# CREE_usb_LED.net
KiCad netlist of a schematic drawn in EAGLE
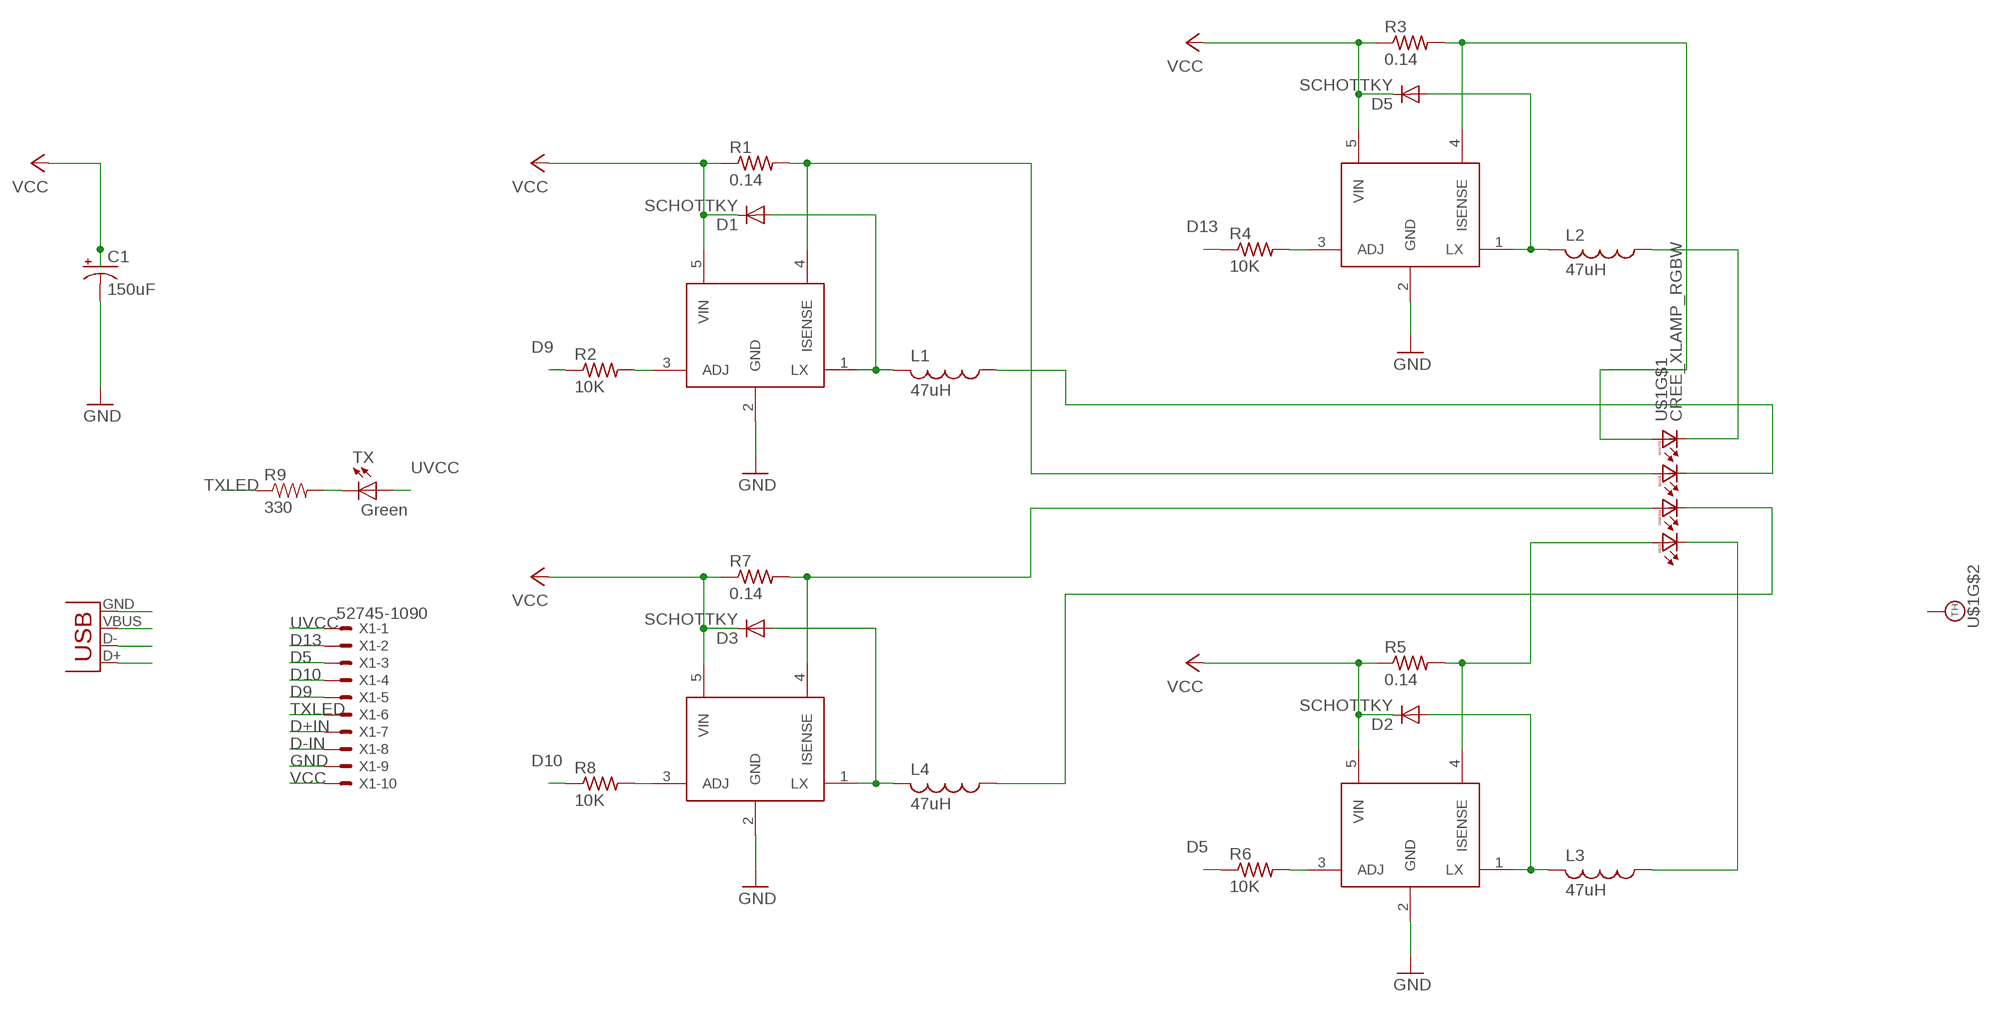
[diagram p0: schematic, sheet 1]

(export (version "E")
  (design (tool "Eeschema 10.0.6"))
  (components
    (comp (ref "C1")
      (value "150uF")
      (footprint "eagle-import:175TMP-0810")
      (libsource (lib "eagle-import") (part "CPOL-US175TMP-0810"))
    )
    (comp (ref "D1")
      (value "SCHOTTKY")
      (footprint "eagle-import:DO214AC")
      (libsource (lib "eagle-import") (part "DIODE-DO214AC"))
    )
    (comp (ref "D2")
      (value "SCHOTTKY")
      (footprint "eagle-import:DO214AC")
      (libsource (lib "eagle-import") (part "DIODE-DO214AC"))
    )
    (comp (ref "D3")
      (value "SCHOTTKY")
      (footprint "eagle-import:DO214AC")
      (libsource (lib "eagle-import") (part "DIODE-DO214AC"))
    )
    (comp (ref "D5")
      (value "SCHOTTKY")
      (footprint "eagle-import:DO214AC")
      (libsource (lib "eagle-import") (part "DIODE-DO214AC"))
    )
    (comp (ref "L1")
      (value "47uH")
      (footprint "eagle-import:TDK6045")
      (libsource (lib "eagle-import") (part "L-US"))
    )
    (comp (ref "L2")
      (value "47uH")
      (footprint "eagle-import:TDK6045")
      (libsource (lib "eagle-import") (part "L-US"))
    )
    (comp (ref "L3")
      (value "47uH")
      (footprint "eagle-import:TDK6045")
      (libsource (lib "eagle-import") (part "L-US"))
    )
    (comp (ref "L4")
      (value "47uH")
      (footprint "eagle-import:TDK6045")
      (libsource (lib "eagle-import") (part "L-US"))
    )
    (comp (ref "R1")
      (value "0.14")
      (footprint "eagle-import:R0805")
      (libsource (lib "eagle-import") (part "R-US_R0805"))
    )
    (comp (ref "R2")
      (value "10K")
      (footprint "eagle-import:R0603")
      (libsource (lib "eagle-import") (part "R-US_R0603"))
    )
    (comp (ref "R3")
      (value "0.14")
      (footprint "eagle-import:R0805")
      (libsource (lib "eagle-import") (part "R-US_R0805"))
    )
    (comp (ref "R4")
      (value "10K")
      (footprint "eagle-import:R0603")
      (libsource (lib "eagle-import") (part "R-US_R0603"))
    )
    (comp (ref "R5")
      (value "0.14")
      (footprint "eagle-import:R0805")
      (libsource (lib "eagle-import") (part "R-US_R0805"))
    )
    (comp (ref "R6")
      (value "10K")
      (footprint "eagle-import:R0603")
      (libsource (lib "eagle-import") (part "R-US_R0603"))
    )
    (comp (ref "R7")
      (value "0.14")
      (footprint "eagle-import:R0805")
      (libsource (lib "eagle-import") (part "R-US_R0805"))
    )
    (comp (ref "R8")
      (value "10K")
      (footprint "eagle-import:R0603")
      (libsource (lib "eagle-import") (part "R-US_R0603"))
    )
    (comp (ref "R9")
      (value "330")
      (footprint "eagle-import:0402-RES")
      (libsource (lib "eagle-import") (part "RESISTOR0402-RES"))
    )
    (comp (ref "TX")
      (value "Green")
      (footprint "eagle-import:LED-0603")
      (libsource (lib "eagle-import") (part "LED0603"))
    )
    (comp (ref "U$1")
      (value "CREE_XLAMP_RGBW")
      (footprint "eagle-import:CREE_XLAMP_XML")
      (libsource (lib "eagle-import") (part "CREE_XLAMP_RGBW"))
    )
    (comp (ref "U$2")
      (value "ZLED7000-LEDDRIVER")
      (footprint "eagle-import:SOT89-5")
      (libsource (lib "eagle-import") (part "ZLED7000-LEDDRIVER"))
    )
    (comp (ref "U$3")
      (value "ZLED7000-LEDDRIVER")
      (footprint "eagle-import:SOT89-5")
      (libsource (lib "eagle-import") (part "ZLED7000-LEDDRIVER"))
    )
    (comp (ref "U$4")
      (value "ZLED7000-LEDDRIVER")
      (footprint "eagle-import:SOT89-5")
      (libsource (lib "eagle-import") (part "ZLED7000-LEDDRIVER"))
    )
    (comp (ref "U$6")
      (value "ZLED7000-LEDDRIVER")
      (footprint "eagle-import:SOT89-5")
      (libsource (lib "eagle-import") (part "ZLED7000-LEDDRIVER"))
    )
    (comp (ref "X1")
      (value "52745-1090")
      (footprint "eagle-import:52745-1090")
      (libsource (lib "eagle-import") (part "52745-1090"))
    )
    (comp (ref "X2")
      (value "USB-MICROB")
      (footprint "eagle-import:USB-MICROB")
      (libsource (lib "eagle-import") (part "USB-MICROB"))
    )
  )
  (nets
    (net (code "1") (name "/D+IN") (class "Default")
      (node (ref "X1") (pin "7") (pinfunction "S_7") (pintype "passive"))
      (node (ref "X2") (pin "D+") (pinfunction "D+_D+") (pintype "bidirectional"))
    )
    (net (code "2") (name "/D-IN") (class "Default")
      (node (ref "X1") (pin "8") (pinfunction "S_8") (pintype "passive"))
      (node (ref "X2") (pin "D-") (pinfunction "D-_D-") (pintype "bidirectional"))
    )
    (net (code "3") (name "/D5") (class "Default")
      (node (ref "R6") (pin "1") (pinfunction "1_1") (pintype "passive"))
      (node (ref "X1") (pin "3") (pinfunction "S_3") (pintype "passive"))
    )
    (net (code "4") (name "/D9") (class "Default")
      (node (ref "R2") (pin "1") (pinfunction "1_1") (pintype "passive"))
      (node (ref "X1") (pin "5") (pinfunction "S_5") (pintype "passive"))
    )
    (net (code "5") (name "/D10") (class "Default")
      (node (ref "R8") (pin "1") (pinfunction "1_1") (pintype "passive"))
      (node (ref "X1") (pin "4") (pinfunction "S_4") (pintype "passive"))
    )
    (net (code "6") (name "/D13") (class "Default")
      (node (ref "R4") (pin "1") (pinfunction "1_1") (pintype "passive"))
      (node (ref "X1") (pin "2") (pinfunction "S_2") (pintype "passive"))
    )
    (net (code "7") (name "/TXLED") (class "Default")
      (node (ref "R9") (pin "1") (pinfunction "1_1") (pintype "passive"))
      (node (ref "X1") (pin "6") (pinfunction "S_6") (pintype "passive"))
    )
    (net (code "8") (name "/UVCC") (class "Default")
      (node (ref "TX") (pin "A") (pinfunction "A_A") (pintype "passive"))
      (node (ref "X1") (pin "1") (pinfunction "S_1") (pintype "passive"))
      (node (ref "X2") (pin "VBUS") (pinfunction "VBUS_VBUS") (pintype "bidirectional"))
    )
    (net (code "9") (name "GND") (class "Default")
      (node (ref "C1") (pin "-") (pinfunction "-_-") (pintype "passive"))
      (node (ref "U$2") (pin "2") (pinfunction "GND_2") (pintype "bidirectional"))
      (node (ref "U$3") (pin "2") (pinfunction "GND_2") (pintype "bidirectional"))
      (node (ref "U$4") (pin "2") (pinfunction "GND_2") (pintype "bidirectional"))
      (node (ref "U$6") (pin "2") (pinfunction "GND_2") (pintype "bidirectional"))
      (node (ref "X1") (pin "9") (pinfunction "S_9") (pintype "passive"))
      (node (ref "X2") (pin "GND") (pinfunction "GND_GND") (pintype "bidirectional"))
    )
    (net (code "10") (name "Net-(R9-Pad2)") (class "Default")
      (node (ref "R9") (pin "2") (pinfunction "2_2") (pintype "passive"))
      (node (ref "TX") (pin "C") (pinfunction "C_C") (pintype "passive"))
    )
    (net (code "11") (name "Net-(U$1A-BA)") (class "Default")
      (node (ref "R1") (pin "2") (pinfunction "2_2") (pintype "passive"))
      (node (ref "U$1") (pin "3") (pinfunction "BA_3") (pintype "passive"))
      (node (ref "U$2") (pin "4") (pinfunction "ISENSE_4") (pintype "bidirectional"))
    )
    (net (code "12") (name "Net-(U$1A-BC)") (class "Default")
      (node (ref "L1") (pin "1") (pinfunction "1_1") (pintype "passive"))
      (node (ref "U$1") (pin "6") (pinfunction "BC_6") (pintype "passive"))
    )
    (net (code "13") (name "Net-(U$1A-GA)") (class "Default")
      (node (ref "R7") (pin "2") (pinfunction "2_2") (pintype "passive"))
      (node (ref "U$1") (pin "2") (pinfunction "GA_2") (pintype "passive"))
      (node (ref "U$4") (pin "4") (pinfunction "ISENSE_4") (pintype "bidirectional"))
    )
    (net (code "14") (name "Net-(U$1A-GC)") (class "Default")
      (node (ref "L4") (pin "1") (pinfunction "1_1") (pintype "passive"))
      (node (ref "U$1") (pin "7") (pinfunction "GC_7") (pintype "passive"))
    )
    (net (code "15") (name "Net-(U$1A-RA)") (class "Default")
      (node (ref "R5") (pin "2") (pinfunction "2_2") (pintype "passive"))
      (node (ref "U$1") (pin "1") (pinfunction "RA_1") (pintype "passive"))
      (node (ref "U$3") (pin "4") (pinfunction "ISENSE_4") (pintype "bidirectional"))
    )
    (net (code "16") (name "Net-(U$1A-RC)") (class "Default")
      (node (ref "L3") (pin "1") (pinfunction "1_1") (pintype "passive"))
      (node (ref "U$1") (pin "8") (pinfunction "RC_8") (pintype "passive"))
    )
    (net (code "17") (name "Net-(U$1A-WA)") (class "Default")
      (node (ref "R3") (pin "2") (pinfunction "2_2") (pintype "passive"))
      (node (ref "U$1") (pin "4") (pinfunction "WA_4") (pintype "passive"))
      (node (ref "U$6") (pin "4") (pinfunction "ISENSE_4") (pintype "bidirectional"))
    )
    (net (code "18") (name "Net-(U$1A-WC)") (class "Default")
      (node (ref "L2") (pin "1") (pinfunction "1_1") (pintype "passive"))
      (node (ref "U$1") (pin "5") (pinfunction "WC_5") (pintype "passive"))
    )
    (net (code "19") (name "Net-(U$2-ADJ)") (class "Default")
      (node (ref "R2") (pin "2") (pinfunction "2_2") (pintype "passive"))
      (node (ref "U$2") (pin "3") (pinfunction "ADJ_3") (pintype "bidirectional"))
    )
    (net (code "20") (name "Net-(U$2-LX)") (class "Default")
      (node (ref "D1") (pin "A") (pinfunction "A_A") (pintype "passive"))
      (node (ref "L1") (pin "2") (pinfunction "2_2") (pintype "passive"))
      (node (ref "U$2") (pin "1") (pinfunction "LX_1") (pintype "bidirectional"))
    )
    (net (code "21") (name "Net-(U$3-ADJ)") (class "Default")
      (node (ref "R6") (pin "2") (pinfunction "2_2") (pintype "passive"))
      (node (ref "U$3") (pin "3") (pinfunction "ADJ_3") (pintype "bidirectional"))
    )
    (net (code "22") (name "Net-(U$3-LX)") (class "Default")
      (node (ref "D2") (pin "A") (pinfunction "A_A") (pintype "passive"))
      (node (ref "L3") (pin "2") (pinfunction "2_2") (pintype "passive"))
      (node (ref "U$3") (pin "1") (pinfunction "LX_1") (pintype "bidirectional"))
    )
    (net (code "23") (name "Net-(U$4-ADJ)") (class "Default")
      (node (ref "R8") (pin "2") (pinfunction "2_2") (pintype "passive"))
      (node (ref "U$4") (pin "3") (pinfunction "ADJ_3") (pintype "bidirectional"))
    )
    (net (code "24") (name "Net-(U$4-LX)") (class "Default")
      (node (ref "D3") (pin "A") (pinfunction "A_A") (pintype "passive"))
      (node (ref "L4") (pin "2") (pinfunction "2_2") (pintype "passive"))
      (node (ref "U$4") (pin "1") (pinfunction "LX_1") (pintype "bidirectional"))
    )
    (net (code "25") (name "Net-(U$6-ADJ)") (class "Default")
      (node (ref "R4") (pin "2") (pinfunction "2_2") (pintype "passive"))
      (node (ref "U$6") (pin "3") (pinfunction "ADJ_3") (pintype "bidirectional"))
    )
    (net (code "26") (name "Net-(U$6-LX)") (class "Default")
      (node (ref "D5") (pin "A") (pinfunction "A_A") (pintype "passive"))
      (node (ref "L2") (pin "2") (pinfunction "2_2") (pintype "passive"))
      (node (ref "U$6") (pin "1") (pinfunction "LX_1") (pintype "bidirectional"))
    )
    (net (code "27") (name "VCC") (class "Default")
      (node (ref "C1") (pin "+") (pinfunction "+_+") (pintype "passive"))
      (node (ref "D1") (pin "C") (pinfunction "C_C") (pintype "passive"))
      (node (ref "D2") (pin "C") (pinfunction "C_C") (pintype "passive"))
      (node (ref "D3") (pin "C") (pinfunction "C_C") (pintype "passive"))
      (node (ref "D5") (pin "C") (pinfunction "C_C") (pintype "passive"))
      (node (ref "R1") (pin "1") (pinfunction "1_1") (pintype "passive"))
      (node (ref "R3") (pin "1") (pinfunction "1_1") (pintype "passive"))
      (node (ref "R5") (pin "1") (pinfunction "1_1") (pintype "passive"))
      (node (ref "R7") (pin "1") (pinfunction "1_1") (pintype "passive"))
      (node (ref "U$2") (pin "5") (pinfunction "VIN_5") (pintype "bidirectional"))
      (node (ref "U$3") (pin "5") (pinfunction "VIN_5") (pintype "bidirectional"))
      (node (ref "U$4") (pin "5") (pinfunction "VIN_5") (pintype "bidirectional"))
      (node (ref "U$6") (pin "5") (pinfunction "VIN_5") (pintype "bidirectional"))
      (node (ref "X1") (pin "10") (pinfunction "S_10") (pintype "passive"))
    )
    (net (code "28") (name "unconnected-(U$1B-TH-PadP$1)") (class "Default")
      (node (ref "U$1") (pin "P$1") (pinfunction "TH_P$1") (pintype "passive"))
    )
  )
)
